# MIPI_CSI.net
KiCad netlist of a schematic drawn in Altium Designer
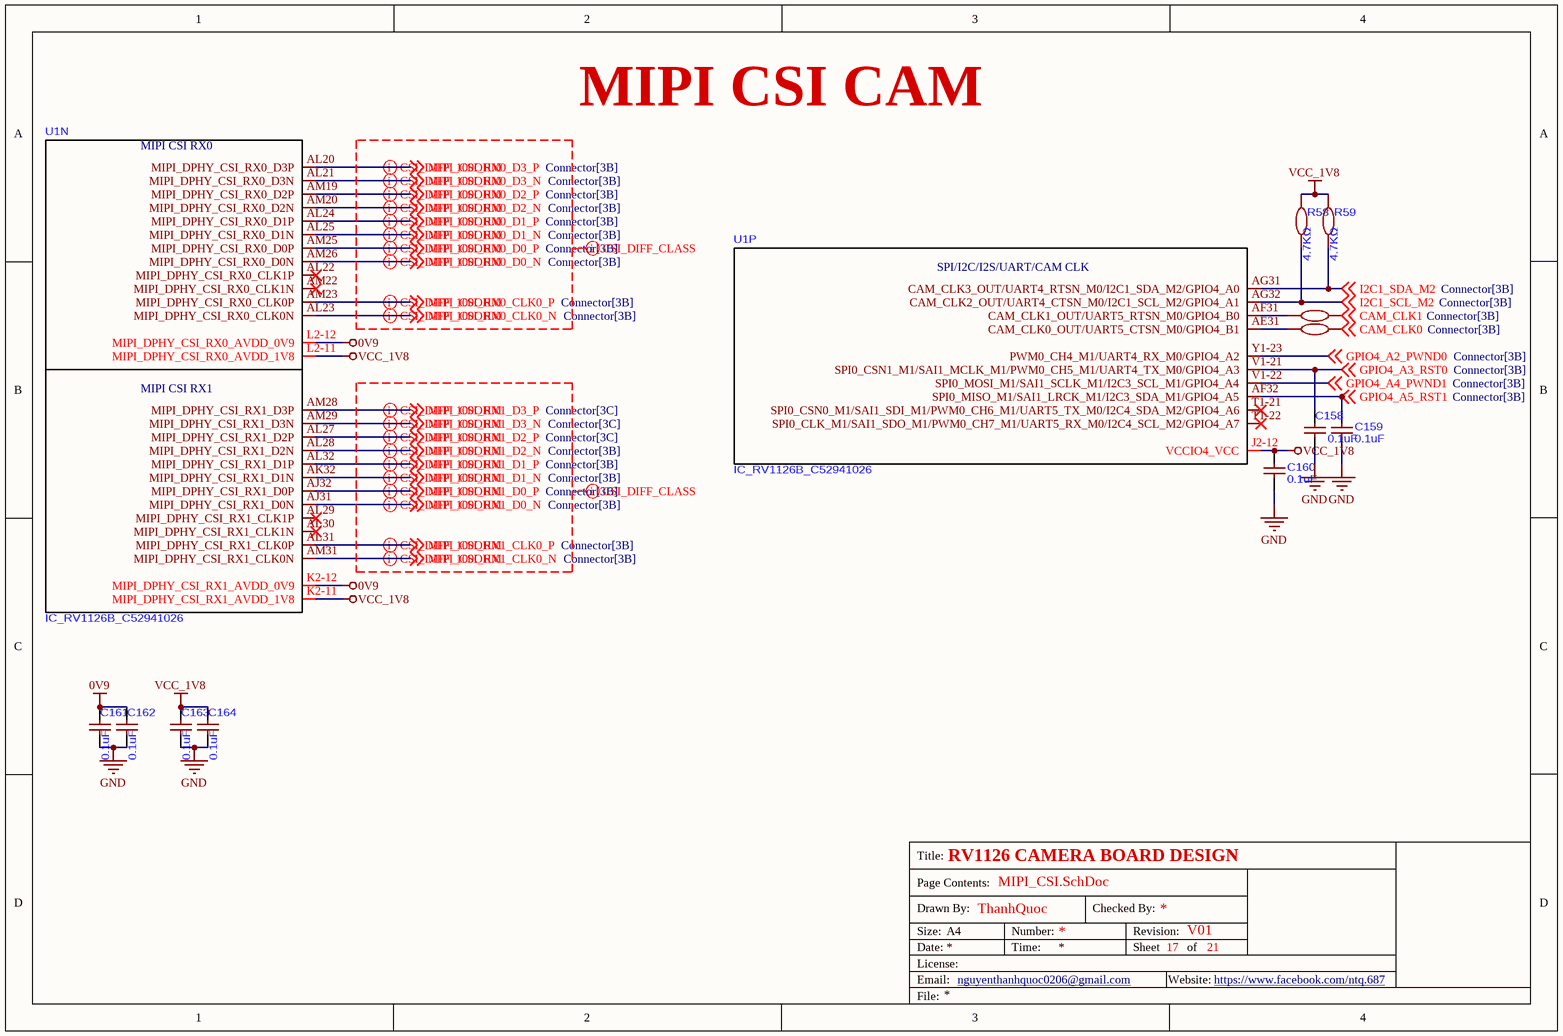
[diagram p0: MIPI_CSI.SchDoc]

(export (version "E")
  (design (tool "Eeschema 10.0.6"))
  (components
    (comp (ref "C158")
      (value "0.1uF")
      (footprint "C0201")
      (description "0.1uF ±10% 6.3V Ceramic Capacitor X5R 0201")
      (libsource (lib "Schlib1") (part "CAP_100nF-6.3V-10%-0201_1"))
    )
    (comp (ref "C159")
      (value "0.1uF")
      (footprint "C0201")
      (description "0.1uF ±10% 6.3V Ceramic Capacitor X5R 0201")
      (libsource (lib "Schlib1") (part "CAP_100nF-6.3V-10%-0201_1"))
    )
    (comp (ref "C160")
      (value "0.1uF")
      (footprint "C0201")
      (description "0.1uF ±10% 6.3V Ceramic Capacitor X5R 0201")
      (libsource (lib "Schlib1") (part "CAP_100nF-6.3V-10%-0201_1"))
    )
    (comp (ref "C161")
      (value "0.1uF")
      (footprint "C0201")
      (description "0.1uF ±10% 6.3V Ceramic Capacitor X5R 0201")
      (libsource (lib "Schlib1") (part "CAP_100nF-6.3V-10%-0201_1"))
    )
    (comp (ref "C162")
      (value "0.1uF")
      (footprint "C0201")
      (description "0.1uF ±10% 6.3V Ceramic Capacitor X5R 0201")
      (libsource (lib "Schlib1") (part "CAP_100nF-6.3V-10%-0201_1"))
    )
    (comp (ref "C163")
      (value "0.1uF")
      (footprint "C0201")
      (description "0.1uF ±10% 6.3V Ceramic Capacitor X5R 0201")
      (libsource (lib "Schlib1") (part "CAP_100nF-6.3V-10%-0201_1"))
    )
    (comp (ref "C164")
      (value "0.1uF")
      (footprint "C0201")
      (description "0.1uF ±10% 6.3V Ceramic Capacitor X5R 0201")
      (libsource (lib "Schlib1") (part "CAP_100nF-6.3V-10%-0201_1"))
    )
    (comp (ref "R58")
      (value "4.7KΩ")
      (footprint "R0201")
      (description "RES 4.7kΩ ±1% 50mW 0201")
      (libsource (lib "Schlib1") (part "RES_4.7K-50mW-1%-0201"))
    )
    (comp (ref "R59")
      (value "4.7KΩ")
      (footprint "R0201")
      (description "RES 4.7kΩ ±1% 50mW 0201")
      (libsource (lib "Schlib1") (part "RES_4.7K-50mW-1%-0201"))
    )
    (comp (ref "R60")
      (value "22Ω")
      (footprint "R0201")
      (description "RES 22Ω ±1% 50mW 0201")
      (libsource (lib "Schlib1") (part "RES_22-50mW-1%-0201"))
    )
    (comp (ref "R61")
      (value "22Ω")
      (footprint "R0201")
      (description "RES 22Ω ±1% 50mW 0201")
      (libsource (lib "Schlib1") (part "RES_22-50mW-1%-0201"))
    )
    (comp (ref "U1")
      (value "IC_RV1126B_C52941026")
      (footprint "CCSP-491_L14.0-W14.0-TL_RV1126B")
      (libsource (lib "Schlib1") (part "IC_RV1126B_C52941026"))
    )
  )
  (nets
    (net (code "1") (name "0V9") (class "Default")
      (node (ref "C161") (pin "2") (pinfunction "2_2") (pintype "passive"))
      (node (ref "C162") (pin "2") (pinfunction "2_2") (pintype "passive"))
      (node (ref "U1") (pin "K2-12") (pinfunction "MIPI_DPHY_CSI_RX1_AVDD_0V9_K2-12") (pintype "passive"))
      (node (ref "U1") (pin "L2-12") (pinfunction "MIPI_DPHY_CSI_RX0_AVDD_0V9_L2-12") (pintype "passive"))
    )
    (net (code "2") (name "CAM_CLK0") (class "Default")
      (node (ref "R61") (pin "2") (pinfunction "2_2") (pintype "passive"))
    )
    (net (code "3") (name "CAM_CLK1") (class "Default")
      (node (ref "R60") (pin "2") (pinfunction "2_2") (pintype "passive"))
    )
    (net (code "4") (name "GND") (class "Default")
      (node (ref "C158") (pin "1") (pinfunction "1_1") (pintype "passive"))
      (node (ref "C159") (pin "1") (pinfunction "1_1") (pintype "passive"))
      (node (ref "C160") (pin "1") (pinfunction "1_1") (pintype "passive"))
      (node (ref "C161") (pin "1") (pinfunction "1_1") (pintype "passive"))
      (node (ref "C162") (pin "1") (pinfunction "1_1") (pintype "passive"))
      (node (ref "C163") (pin "1") (pinfunction "1_1") (pintype "passive"))
      (node (ref "C164") (pin "1") (pinfunction "1_1") (pintype "passive"))
    )
    (net (code "5") (name "GPIO4_A2_PWND0") (class "Default")
      (node (ref "U1") (pin "Y1-23") (pinfunction "PWM0_CH4_M1/UART4_RX_M0/GPIO4_A2_Y1-23") (pintype "passive"))
    )
    (net (code "6") (name "GPIO4_A3_RST0") (class "Default")
      (node (ref "C158") (pin "2") (pinfunction "2_2") (pintype "passive"))
      (node (ref "U1") (pin "V1-21") (pinfunction "SPI0_CSN1_M1/SAI1_MCLK_M1/PWM0_CH5_M1/UART4_TX_M0/GPIO4_A3_V1-21") (pintype "passive"))
    )
    (net (code "7") (name "GPIO4_A4_PWND1") (class "Default")
      (node (ref "U1") (pin "V1-22") (pinfunction "SPI0_MOSI_M1/SAI1_SCLK_M1/I2C3_SCL_M1/GPIO4_A4_V1-22") (pintype "passive"))
    )
    (net (code "8") (name "GPIO4_A5_RST1") (class "Default")
      (node (ref "C159") (pin "2") (pinfunction "2_2") (pintype "passive"))
      (node (ref "U1") (pin "AF32") (pinfunction "SPI0_MISO_M1/SAI1_LRCK_M1/I2C3_SDA_M1/GPIO4_A5_AF32") (pintype "passive"))
    )
    (net (code "9") (name "I2C1_SCL_M2") (class "Default")
      (node (ref "R58") (pin "1") (pinfunction "1_1") (pintype "passive"))
      (node (ref "U1") (pin "AG32") (pinfunction "CAM_CLK2_OUT/UART4_CTSN_M0/I2C1_SCL_M2/GPIO4_A1_AG32") (pintype "passive"))
    )
    (net (code "10") (name "I2C1_SDA_M2") (class "Default")
      (node (ref "R59") (pin "1") (pinfunction "1_1") (pintype "passive"))
      (node (ref "U1") (pin "AG31") (pinfunction "CAM_CLK3_OUT/UART4_RTSN_M0/I2C1_SDA_M2/GPIO4_A0_AG31") (pintype "passive"))
    )
    (net (code "11") (name "MIPI_CSI_RX0_CLK0_N") (class "Default")
      (node (ref "U1") (pin "AL23") (pinfunction "MIPI_DPHY_CSI_RX0_CLK0N_AL23") (pintype "passive"))
    )
    (net (code "12") (name "MIPI_CSI_RX0_CLK0_P") (class "Default")
      (node (ref "U1") (pin "AM23") (pinfunction "MIPI_DPHY_CSI_RX0_CLK0P_AM23") (pintype "passive"))
    )
    (net (code "13") (name "MIPI_CSI_RX0_D0_N") (class "Default")
      (node (ref "U1") (pin "AM26") (pinfunction "MIPI_DPHY_CSI_RX0_D0N_AM26") (pintype "passive"))
    )
    (net (code "14") (name "MIPI_CSI_RX0_D0_P") (class "Default")
      (node (ref "U1") (pin "AM25") (pinfunction "MIPI_DPHY_CSI_RX0_D0P_AM25") (pintype "passive"))
    )
    (net (code "15") (name "MIPI_CSI_RX0_D1_N") (class "Default")
      (node (ref "U1") (pin "AL25") (pinfunction "MIPI_DPHY_CSI_RX0_D1N_AL25") (pintype "passive"))
    )
    (net (code "16") (name "MIPI_CSI_RX0_D1_P") (class "Default")
      (node (ref "U1") (pin "AL24") (pinfunction "MIPI_DPHY_CSI_RX0_D1P_AL24") (pintype "passive"))
    )
    (net (code "17") (name "MIPI_CSI_RX0_D2_N") (class "Default")
      (node (ref "U1") (pin "AM20") (pinfunction "MIPI_DPHY_CSI_RX0_D2N_AM20") (pintype "passive"))
    )
    (net (code "18") (name "MIPI_CSI_RX0_D2_P") (class "Default")
      (node (ref "U1") (pin "AM19") (pinfunction "MIPI_DPHY_CSI_RX0_D2P_AM19") (pintype "passive"))
    )
    (net (code "19") (name "MIPI_CSI_RX0_D3_N") (class "Default")
      (node (ref "U1") (pin "AL21") (pinfunction "MIPI_DPHY_CSI_RX0_D3N_AL21") (pintype "passive"))
    )
    (net (code "20") (name "MIPI_CSI_RX0_D3_P") (class "Default")
      (node (ref "U1") (pin "AL20") (pinfunction "MIPI_DPHY_CSI_RX0_D3P_AL20") (pintype "passive"))
    )
    (net (code "21") (name "MIPI_CSI_RX1_CLK0_N") (class "Default")
      (node (ref "U1") (pin "AM31") (pinfunction "MIPI_DPHY_CSI_RX1_CLK0N_AM31") (pintype "passive"))
    )
    (net (code "22") (name "MIPI_CSI_RX1_CLK0_P") (class "Default")
      (node (ref "U1") (pin "AL31") (pinfunction "MIPI_DPHY_CSI_RX1_CLK0P_AL31") (pintype "passive"))
    )
    (net (code "23") (name "MIPI_CSI_RX1_D0_N") (class "Default")
      (node (ref "U1") (pin "AJ31") (pinfunction "MIPI_DPHY_CSI_RX1_D0N_AJ31") (pintype "passive"))
    )
    (net (code "24") (name "MIPI_CSI_RX1_D0_P") (class "Default")
      (node (ref "U1") (pin "AJ32") (pinfunction "MIPI_DPHY_CSI_RX1_D0P_AJ32") (pintype "passive"))
    )
    (net (code "25") (name "MIPI_CSI_RX1_D1_N") (class "Default")
      (node (ref "U1") (pin "AK32") (pinfunction "MIPI_DPHY_CSI_RX1_D1N_AK32") (pintype "passive"))
    )
    (net (code "26") (name "MIPI_CSI_RX1_D1_P") (class "Default")
      (node (ref "U1") (pin "AL32") (pinfunction "MIPI_DPHY_CSI_RX1_D1P_AL32") (pintype "passive"))
    )
    (net (code "27") (name "MIPI_CSI_RX1_D2_N") (class "Default")
      (node (ref "U1") (pin "AL28") (pinfunction "MIPI_DPHY_CSI_RX1_D2N_AL28") (pintype "passive"))
    )
    (net (code "28") (name "MIPI_CSI_RX1_D2_P") (class "Default")
      (node (ref "U1") (pin "AL27") (pinfunction "MIPI_DPHY_CSI_RX1_D2P_AL27") (pintype "passive"))
    )
    (net (code "29") (name "MIPI_CSI_RX1_D3_N") (class "Default")
      (node (ref "U1") (pin "AM29") (pinfunction "MIPI_DPHY_CSI_RX1_D3N_AM29") (pintype "passive"))
    )
    (net (code "30") (name "MIPI_CSI_RX1_D3_P") (class "Default")
      (node (ref "U1") (pin "AM28") (pinfunction "MIPI_DPHY_CSI_RX1_D3P_AM28") (pintype "passive"))
    )
    (net (code "31") (name "Net-(U1P-CAM_CLK0_OUT{slash}UART5_CTSN_M0{slash}GPIO4_B1)") (class "Default")
      (node (ref "R61") (pin "1") (pinfunction "1_1") (pintype "passive"))
      (node (ref "U1") (pin "AE31") (pinfunction "CAM_CLK0_OUT/UART5_CTSN_M0/GPIO4_B1_AE31") (pintype "passive"))
    )
    (net (code "32") (name "Net-(U1P-CAM_CLK1_OUT{slash}UART5_RTSN_M0{slash}GPIO4_B0)") (class "Default")
      (node (ref "R60") (pin "1") (pinfunction "1_1") (pintype "passive"))
      (node (ref "U1") (pin "AF31") (pinfunction "CAM_CLK1_OUT/UART5_RTSN_M0/GPIO4_B0_AF31") (pintype "passive"))
    )
    (net (code "33") (name "VCC_1V8") (class "Default")
      (node (ref "C160") (pin "2") (pinfunction "2_2") (pintype "passive"))
      (node (ref "C163") (pin "2") (pinfunction "2_2") (pintype "passive"))
      (node (ref "C164") (pin "2") (pinfunction "2_2") (pintype "passive"))
      (node (ref "R58") (pin "2") (pinfunction "2_2") (pintype "passive"))
      (node (ref "R59") (pin "2") (pinfunction "2_2") (pintype "passive"))
      (node (ref "U1") (pin "J2-12") (pinfunction "VCCIO4_VCC_J2-12") (pintype "passive"))
      (node (ref "U1") (pin "K2-11") (pinfunction "MIPI_DPHY_CSI_RX1_AVDD_1V8_K2-11") (pintype "passive"))
      (node (ref "U1") (pin "L2-11") (pinfunction "MIPI_DPHY_CSI_RX0_AVDD_1V8_L2-11") (pintype "passive"))
    )
    (net (code "34") (name "unconnected-(U1N-MIPI_DPHY_CSI_RX0_CLK1N-PadAM22)") (class "Default")
      (node (ref "U1") (pin "AM22") (pinfunction "MIPI_DPHY_CSI_RX0_CLK1N_AM22") (pintype "passive+no_connect"))
    )
    (net (code "35") (name "unconnected-(U1N-MIPI_DPHY_CSI_RX0_CLK1P-PadAL22)") (class "Default")
      (node (ref "U1") (pin "AL22") (pinfunction "MIPI_DPHY_CSI_RX0_CLK1P_AL22") (pintype "passive+no_connect"))
    )
    (net (code "36") (name "unconnected-(U1N-MIPI_DPHY_CSI_RX1_CLK1N-PadAL30)") (class "Default")
      (node (ref "U1") (pin "AL30") (pinfunction "MIPI_DPHY_CSI_RX1_CLK1N_AL30") (pintype "passive+no_connect"))
    )
    (net (code "37") (name "unconnected-(U1N-MIPI_DPHY_CSI_RX1_CLK1P-PadAL29)") (class "Default")
      (node (ref "U1") (pin "AL29") (pinfunction "MIPI_DPHY_CSI_RX1_CLK1P_AL29") (pintype "passive+no_connect"))
    )
    (net (code "38") (name "unconnected-(U1P-SPI0_CLK_M1{slash}SAI1_SDO_M1{slash}PWM0_CH7_M1{slash}UART5_RX_M0{slash}I2C4_SCL_M2{slash}GPIO4_A7-PadT1-22)") (class "Default")
      (node (ref "U1") (pin "T1-22") (pinfunction "SPI0_CLK_M1/SAI1_SDO_M1/PWM0_CH7_M1/UART5_RX_M0/I2C4_SCL_M2/GPIO4_A7_T1-22") (pintype "passive+no_connect"))
    )
    (net (code "39") (name "unconnected-(U1P-SPI0_CSN0_M1{slash}SAI1_SDI_M1{slash}PWM0_CH6_M1{slash}UART5_TX_M0{slash}I2C4_SDA_M2{slash}GPIO4_A6-PadT1-21)") (class "Default")
      (node (ref "U1") (pin "T1-21") (pinfunction "SPI0_CSN0_M1/SAI1_SDI_M1/PWM0_CH6_M1/UART5_TX_M0/I2C4_SDA_M2/GPIO4_A6_T1-21") (pintype "passive+no_connect"))
    )
  )
)
